# se7en.net
KiCad netlist of a schematic drawn in EAGLE
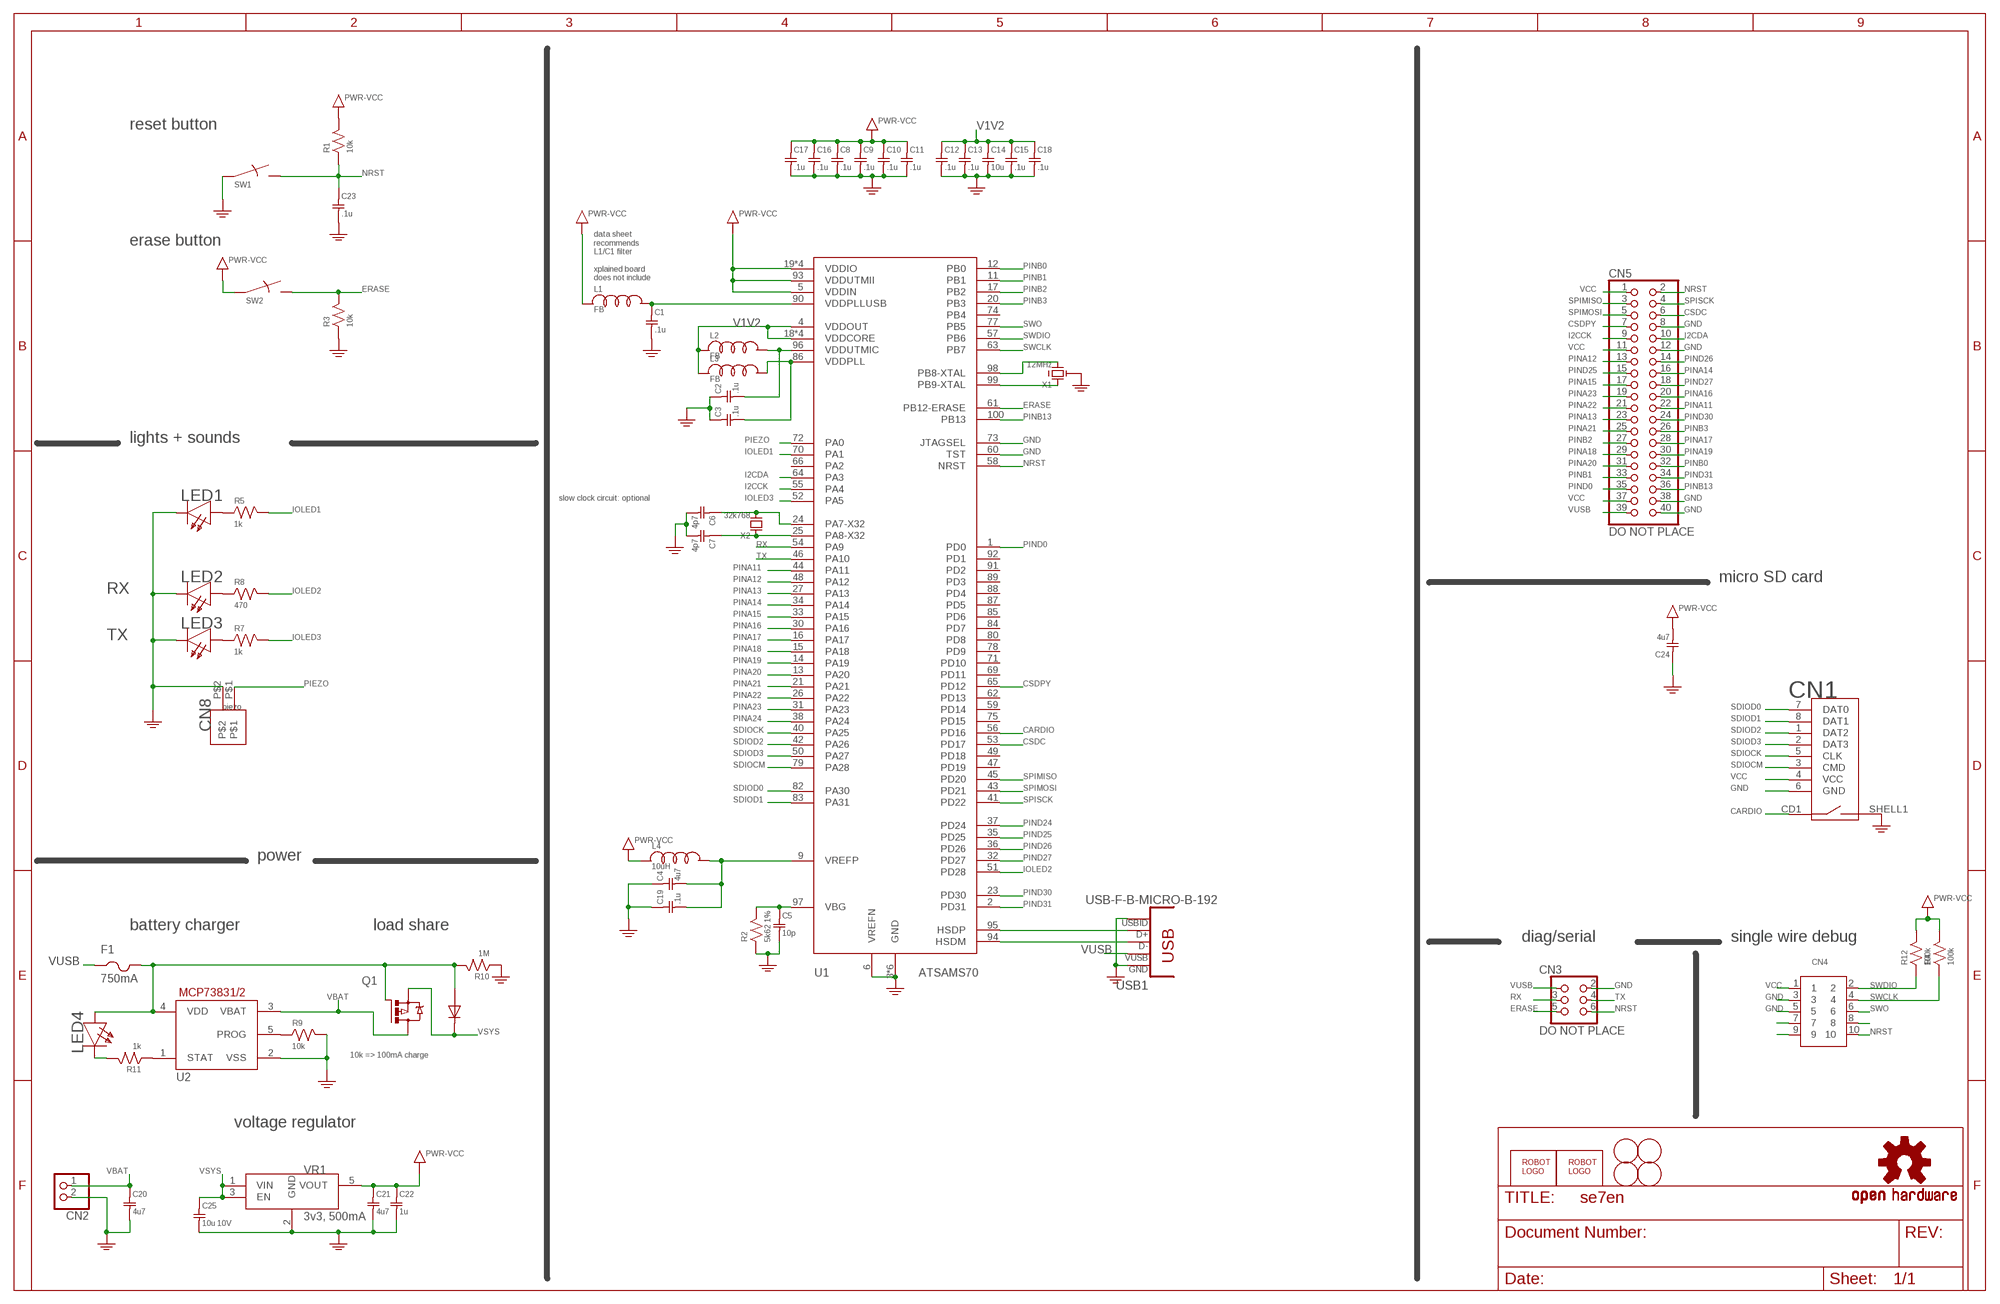
[diagram p0: schematic, sheet 1]

(export (version "E")
  (design (tool "Eeschema 10.0.6"))
  (components
    (comp (ref "C1")
      (value ".1u")
      (footprint "eagle-import:SMD0402")
      (libsource (lib "eagle-import") (part "C-0402"))
    )
    (comp (ref "C2")
      (value ".1u")
      (footprint "eagle-import:SMD0402")
      (libsource (lib "eagle-import") (part "C-0402"))
    )
    (comp (ref "C3")
      (value ".1u")
      (footprint "eagle-import:SMD0402")
      (libsource (lib "eagle-import") (part "C-0402"))
    )
    (comp (ref "C4")
      (value "4u7")
      (footprint "eagle-import:SMD0603")
      (libsource (lib "eagle-import") (part "C0603"))
    )
    (comp (ref "C5")
      (value "10p")
      (footprint "eagle-import:SMD0402")
      (libsource (lib "eagle-import") (part "C-0402"))
    )
    (comp (ref "C6")
      (value "4p7")
      (footprint "eagle-import:SMD0402")
      (libsource (lib "eagle-import") (part "C-0402"))
    )
    (comp (ref "C7")
      (value "4p7")
      (footprint "eagle-import:SMD0402")
      (libsource (lib "eagle-import") (part "C-0402"))
    )
    (comp (ref "C8")
      (value ".1u")
      (footprint "eagle-import:SMD0402")
      (libsource (lib "eagle-import") (part "C-0402"))
    )
    (comp (ref "C9")
      (value ".1u")
      (footprint "eagle-import:SMD0402")
      (libsource (lib "eagle-import") (part "C-0402"))
    )
    (comp (ref "C10")
      (value ".1u")
      (footprint "eagle-import:SMD0402")
      (libsource (lib "eagle-import") (part "C-0402"))
    )
    (comp (ref "C11")
      (value ".1u")
      (footprint "eagle-import:SMD0402")
      (libsource (lib "eagle-import") (part "C-0402"))
    )
    (comp (ref "C12")
      (value ".1u")
      (footprint "eagle-import:SMD0402")
      (libsource (lib "eagle-import") (part "C-0402"))
    )
    (comp (ref "C13")
      (value ".1u")
      (footprint "eagle-import:SMD0402")
      (libsource (lib "eagle-import") (part "C-0402"))
    )
    (comp (ref "C14")
      (value "10u")
      (footprint "eagle-import:SMD0603")
      (libsource (lib "eagle-import") (part "C0603"))
    )
    (comp (ref "C15")
      (value ".1u")
      (footprint "eagle-import:SMD0402")
      (libsource (lib "eagle-import") (part "C-0402"))
    )
    (comp (ref "C16")
      (value ".1u")
      (footprint "eagle-import:SMD0402")
      (libsource (lib "eagle-import") (part "C-0402"))
    )
    (comp (ref "C17")
      (value ".1u")
      (footprint "eagle-import:SMD0402")
      (libsource (lib "eagle-import") (part "C-0402"))
    )
    (comp (ref "C18")
      (value ".1u")
      (footprint "eagle-import:SMD0402")
      (libsource (lib "eagle-import") (part "C-0402"))
    )
    (comp (ref "C19")
      (value ".1u")
      (footprint "eagle-import:SMD0402")
      (libsource (lib "eagle-import") (part "C-0402"))
    )
    (comp (ref "C20")
      (value "4u7")
      (footprint "eagle-import:SMD0603")
      (libsource (lib "eagle-import") (part "C0603"))
    )
    (comp (ref "C21")
      (value "4u7")
      (footprint "eagle-import:SMD0603")
      (libsource (lib "eagle-import") (part "C0603"))
    )
    (comp (ref "C22")
      (value "1u")
      (footprint "eagle-import:SMD0603")
      (libsource (lib "eagle-import") (part "C0603"))
    )
    (comp (ref "C23")
      (value ".1u")
      (footprint "eagle-import:SMD0402")
      (libsource (lib "eagle-import") (part "C-0402"))
    )
    (comp (ref "C24")
      (value "4u7")
      (footprint "eagle-import:SMD0603")
      (libsource (lib "eagle-import") (part "C0603"))
    )
    (comp (ref "C25")
      (value "10u 10V")
      (footprint "eagle-import:SMD0603")
      (libsource (lib "eagle-import") (part "C0603"))
    )
    (comp (ref "CN1")
      (value "MICROSD-EJECT")
      (footprint "eagle-import:MICROSD_EJECTOR")
      (libsource (lib "eagle-import") (part "MICROSD-EJECT"))
    )
    (comp (ref "CN2")
      (value "JST_2PIN-SMT-RA")
      (footprint "eagle-import:JST-PH-2-SMT-RA")
      (libsource (lib "eagle-import") (part "JST_2PIN-SMT-RA"))
    )
    (comp (ref "CN3")
      (value "DO NOT PLACE")
      (footprint "eagle-import:HEADER-3X2-POGO")
      (libsource (lib "eagle-import") (part "HEADER-3X2-POGO"))
    )
    (comp (ref "CN4")
      (value "DO NOT PLACE")
      (footprint "eagle-import:M127-5X2-F")
      (libsource (lib "eagle-import") (part "HEADER-5X2-SMD-F"))
    )
    (comp (ref "CN5")
      (value "DO NOT PLACE")
      (footprint "eagle-import:2X20")
      (libsource (lib "eagle-import") (part "PINHD-2X20"))
    )
    (comp (ref "CN8")
      (value "DO NOT PLACE")
      (footprint "eagle-import:HEADER-1X2-THM-TIGHT")
      (libsource (lib "eagle-import") (part "HEADER-1X2M254"))
    )
    (comp (ref "F1")
      (value "750mA")
      (footprint "eagle-import:SMD1206")
      (libsource (lib "eagle-import") (part "FUSE"))
    )
    (comp (ref "L1")
      (value "FB")
      (footprint "eagle-import:SMD0402")
      (libsource (lib "eagle-import") (part "L-0402"))
    )
    (comp (ref "L2")
      (value "FB")
      (footprint "eagle-import:SMD0402")
      (libsource (lib "eagle-import") (part "L-0402"))
    )
    (comp (ref "L3")
      (value "FB")
      (footprint "eagle-import:SMD0402")
      (libsource (lib "eagle-import") (part "L-0402"))
    )
    (comp (ref "L4")
      (value "10uH")
      (footprint "eagle-import:SMD0603")
      (libsource (lib "eagle-import") (part "LSMD0603"))
    )
    (comp (ref "LED1")
      (value "white")
      (footprint "eagle-import:SMD0603D")
      (libsource (lib "eagle-import") (part "LED"))
    )
    (comp (ref "LED2")
      (value "green")
      (footprint "eagle-import:SMD0603D")
      (libsource (lib "eagle-import") (part "LED"))
    )
    (comp (ref "LED3")
      (value "orange")
      (footprint "eagle-import:SMD0603D")
      (libsource (lib "eagle-import") (part "LED"))
    )
    (comp (ref "LED4")
      (value "RED")
      (footprint "eagle-import:SMD0603D")
      (libsource (lib "eagle-import") (part "LED"))
    )
    (comp (ref "LOGO$1")
      (value "OSHW-LOGOM")
      (footprint "eagle-import:OSHW-LOGO-M")
      (libsource (lib "eagle-import") (part "OSHW-LOGOM"))
    )
    (comp (ref "Q1")
      (value "FDC6392S")
      (footprint "eagle-import:SOT-23-6")
      (libsource (lib "eagle-import") (part "FDC6392S"))
    )
    (comp (ref "R1")
      (value "10k")
      (footprint "eagle-import:SMD0402")
      (libsource (lib "eagle-import") (part "R-0402"))
    )
    (comp (ref "R2")
      (value "5k62 1%")
      (footprint "eagle-import:SMD0402")
      (libsource (lib "eagle-import") (part "R-0402"))
    )
    (comp (ref "R3")
      (value "10k")
      (footprint "eagle-import:SMD0402")
      (libsource (lib "eagle-import") (part "R-0402"))
    )
    (comp (ref "R4")
      (value "100k")
      (footprint "eagle-import:SMD0402")
      (libsource (lib "eagle-import") (part "R-0402"))
    )
    (comp (ref "R5")
      (value "1k")
      (footprint "eagle-import:SMD0402")
      (libsource (lib "eagle-import") (part "R-0402"))
    )
    (comp (ref "R7")
      (value "1k")
      (footprint "eagle-import:SMD0402")
      (libsource (lib "eagle-import") (part "R-0402"))
    )
    (comp (ref "R8")
      (value "470")
      (footprint "eagle-import:SMD0402")
      (libsource (lib "eagle-import") (part "R-0402"))
    )
    (comp (ref "R9")
      (value "10k")
      (footprint "eagle-import:SMD0402")
      (libsource (lib "eagle-import") (part "R-0402"))
    )
    (comp (ref "R10")
      (value "1M")
      (footprint "eagle-import:SMD0402")
      (libsource (lib "eagle-import") (part "R-0402"))
    )
    (comp (ref "R11")
      (value "1k")
      (footprint "eagle-import:SMD0402")
      (libsource (lib "eagle-import") (part "R-0402"))
    )
    (comp (ref "R12")
      (value "100k")
      (footprint "eagle-import:SMD0402")
      (libsource (lib "eagle-import") (part "R-0402"))
    )
    (comp (ref "SW1")
      (value "SWITCHKMR211")
      (footprint "eagle-import:KMR211")
      (libsource (lib "eagle-import") (part "SWITCHKMR211"))
    )
    (comp (ref "SW2")
      (value "SWITCHKMR211")
      (footprint "eagle-import:KMR211")
      (libsource (lib "eagle-import") (part "SWITCHKMR211"))
    )
    (comp (ref "U$1")
      (value "ROBOTMAN-LOGO2")
      (footprint "eagle-import:ROBOTMAN-LOGO2")
      (libsource (lib "eagle-import") (part "ROBOTMAN-LOGO2"))
    )
    (comp (ref "U$2")
      (value "FIDUCIAL")
      (footprint "eagle-import:FIDUCIAL_1MM")
      (libsource (lib "eagle-import") (part "FIDUCIAL"))
    )
    (comp (ref "U$3")
      (value "ROBOTMAN-LOGO2")
      (footprint "eagle-import:ROBOTMAN-LOGO2")
      (libsource (lib "eagle-import") (part "ROBOTMAN-LOGO2"))
    )
    (comp (ref "U$4")
      (value "FIDUCIAL")
      (footprint "eagle-import:FIDUCIAL_1MM")
      (libsource (lib "eagle-import") (part "FIDUCIAL"))
    )
    (comp (ref "U$5")
      (value "FIDUCIAL")
      (footprint "eagle-import:FIDUCIAL_1MM")
      (libsource (lib "eagle-import") (part "FIDUCIAL"))
    )
    (comp (ref "U$6")
      (value "FIDUCIAL")
      (footprint "eagle-import:FIDUCIAL_1MM")
      (libsource (lib "eagle-import") (part "FIDUCIAL"))
    )
    (comp (ref "U1")
      (value "ATSAMS70")
      (footprint "eagle-import:TQFP-100-14X14MM")
      (libsource (lib "eagle-import") (part "ATSAME70"))
    )
    (comp (ref "U2")
      (value "MCP73831")
      (footprint "eagle-import:SOT-23-5")
      (libsource (lib "eagle-import") (part "MCP73831"))
    )
    (comp (ref "USB1")
      (value "USB-F-B-MICRO-B-192")
      (footprint "eagle-import:USB-MICRO-B-192")
      (libsource (lib "eagle-import") (part "USB-F-B-MICRO-B-192"))
    )
    (comp (ref "VR1")
      (value "3v3, 500mA")
      (footprint "eagle-import:SOT-23-5")
      (libsource (lib "eagle-import") (part "REGULATOR4-SOT23"))
    )
    (comp (ref "X1")
      (value "12MHz")
      (footprint "eagle-import:RESONATOR-CSTCE")
      (libsource (lib "eagle-import") (part "RESONATORCTCE"))
    )
    (comp (ref "X2")
      (value "32k768")
      (footprint "eagle-import:XTAL-32X15")
      (libsource (lib "eagle-import") (part "XTAL32X15"))
    )
  )
  (nets
    (net (code "1") (name "/CARDIO") (class "Default")
      (node (ref "CN1") (pin "CD1") (pinfunction "SW1_CD1") (pintype "bidirectional"))
      (node (ref "U1") (pin "56") (pinfunction "PD16_56") (pintype "bidirectional"))
    )
    (net (code "2") (name "/CSDC") (class "Default")
      (node (ref "CN5") (pin "6") (pinfunction "6_6") (pintype "passive"))
      (node (ref "U1") (pin "53") (pinfunction "PD17_53") (pintype "bidirectional"))
    )
    (net (code "3") (name "/CSDPY") (class "Default")
      (node (ref "CN5") (pin "7") (pinfunction "7_7") (pintype "passive"))
      (node (ref "U1") (pin "65") (pinfunction "PD12_65") (pintype "bidirectional"))
    )
    (net (code "4") (name "/ERASE") (class "Default")
      (node (ref "CN3") (pin "5") (pinfunction "P$5_5") (pintype "passive"))
      (node (ref "R3") (pin "2") (pinfunction "P$2_2") (pintype "passive"))
      (node (ref "SW2") (pin "2") (pinfunction "P$2_2") (pintype "passive"))
      (node (ref "SW2") (pin "4") (pinfunction "P$2_4") (pintype "passive"))
      (node (ref "U1") (pin "61") (pinfunction "PB12-ERASE_61") (pintype "bidirectional"))
    )
    (net (code "5") (name "/I2CCK") (class "Default")
      (node (ref "CN5") (pin "9") (pinfunction "9_9") (pintype "passive"))
      (node (ref "U1") (pin "55") (pinfunction "PA4_55") (pintype "bidirectional"))
    )
    (net (code "6") (name "/I2CDA") (class "Default")
      (node (ref "CN5") (pin "10") (pinfunction "10_10") (pintype "passive"))
      (node (ref "U1") (pin "64") (pinfunction "PA3_64") (pintype "bidirectional"))
    )
    (net (code "7") (name "/IOLED1") (class "Default")
      (node (ref "R5") (pin "2") (pinfunction "P$2_2") (pintype "passive"))
      (node (ref "U1") (pin "70") (pinfunction "PA1_70") (pintype "bidirectional"))
    )
    (net (code "8") (name "/IOLED2") (class "Default")
      (node (ref "R8") (pin "2") (pinfunction "P$2_2") (pintype "passive"))
      (node (ref "U1") (pin "51") (pinfunction "PD28_51") (pintype "bidirectional"))
    )
    (net (code "9") (name "/IOLED3") (class "Default")
      (node (ref "R7") (pin "2") (pinfunction "P$2_2") (pintype "passive"))
      (node (ref "U1") (pin "52") (pinfunction "PA5_52") (pintype "bidirectional"))
    )
    (net (code "10") (name "/NRST") (class "Default")
      (node (ref "C23") (pin "1") (pinfunction "P$1_1") (pintype "passive"))
      (node (ref "CN3") (pin "6") (pinfunction "P$6_6") (pintype "passive"))
      (node (ref "CN4") (pin "10") (pinfunction "10_10") (pintype "passive"))
      (node (ref "CN5") (pin "2") (pinfunction "2_2") (pintype "passive"))
      (node (ref "R1") (pin "1") (pinfunction "P$1_1") (pintype "passive"))
      (node (ref "SW1") (pin "2") (pinfunction "P$2_2") (pintype "passive"))
      (node (ref "SW1") (pin "4") (pinfunction "P$2_4") (pintype "passive"))
      (node (ref "U1") (pin "58") (pinfunction "NRST_58") (pintype "bidirectional"))
    )
    (net (code "11") (name "/PIEZO") (class "Default")
      (node (ref "CN8") (pin "P$1") (pinfunction "P$1_P$1") (pintype "bidirectional"))
      (node (ref "U1") (pin "72") (pinfunction "PA0_72") (pintype "bidirectional"))
    )
    (net (code "12") (name "/PINA11") (class "Default")
      (node (ref "CN5") (pin "22") (pinfunction "22_22") (pintype "passive"))
      (node (ref "U1") (pin "44") (pinfunction "PA11_44") (pintype "bidirectional"))
    )
    (net (code "13") (name "/PINA12") (class "Default")
      (node (ref "CN5") (pin "13") (pinfunction "13_13") (pintype "passive"))
      (node (ref "U1") (pin "48") (pinfunction "PA12_48") (pintype "bidirectional"))
    )
    (net (code "14") (name "/PINA13") (class "Default")
      (node (ref "CN5") (pin "23") (pinfunction "23_23") (pintype "passive"))
      (node (ref "U1") (pin "27") (pinfunction "PA13_27") (pintype "bidirectional"))
    )
    (net (code "15") (name "/PINA14") (class "Default")
      (node (ref "CN5") (pin "16") (pinfunction "16_16") (pintype "passive"))
      (node (ref "U1") (pin "34") (pinfunction "PA14_34") (pintype "bidirectional"))
    )
    (net (code "16") (name "/PINA15") (class "Default")
      (node (ref "CN5") (pin "17") (pinfunction "17_17") (pintype "passive"))
      (node (ref "U1") (pin "33") (pinfunction "PA15_33") (pintype "bidirectional"))
    )
    (net (code "17") (name "/PINA16") (class "Default")
      (node (ref "CN5") (pin "20") (pinfunction "20_20") (pintype "passive"))
      (node (ref "U1") (pin "30") (pinfunction "PA16_30") (pintype "bidirectional"))
    )
    (net (code "18") (name "/PINA17") (class "Default")
      (node (ref "CN5") (pin "28") (pinfunction "28_28") (pintype "passive"))
      (node (ref "U1") (pin "16") (pinfunction "PA17_16") (pintype "bidirectional"))
    )
    (net (code "19") (name "/PINA18") (class "Default")
      (node (ref "CN5") (pin "29") (pinfunction "29_29") (pintype "passive"))
      (node (ref "U1") (pin "15") (pinfunction "PA18_15") (pintype "bidirectional"))
    )
    (net (code "20") (name "/PINA19") (class "Default")
      (node (ref "CN5") (pin "30") (pinfunction "30_30") (pintype "passive"))
      (node (ref "U1") (pin "14") (pinfunction "PA19_14") (pintype "bidirectional"))
    )
    (net (code "21") (name "/PINA20") (class "Default")
      (node (ref "CN5") (pin "31") (pinfunction "31_31") (pintype "passive"))
      (node (ref "U1") (pin "13") (pinfunction "PA20_13") (pintype "bidirectional"))
    )
    (net (code "22") (name "/PINA21") (class "Default")
      (node (ref "CN5") (pin "25") (pinfunction "25_25") (pintype "passive"))
      (node (ref "U1") (pin "21") (pinfunction "PA21_21") (pintype "bidirectional"))
    )
    (net (code "23") (name "/PINA22") (class "Default")
      (node (ref "CN5") (pin "21") (pinfunction "21_21") (pintype "passive"))
      (node (ref "U1") (pin "26") (pinfunction "PA22_26") (pintype "bidirectional"))
    )
    (net (code "24") (name "/PINA23") (class "Default")
      (node (ref "CN5") (pin "19") (pinfunction "19_19") (pintype "passive"))
      (node (ref "U1") (pin "31") (pinfunction "PA23_31") (pintype "bidirectional"))
    )
    (net (code "25") (name "/PINA24") (class "Default")
      (node (ref "U1") (pin "38") (pinfunction "PA24_38") (pintype "bidirectional"))
    )
    (net (code "26") (name "/PINB0") (class "Default")
      (node (ref "CN5") (pin "32") (pinfunction "32_32") (pintype "passive"))
      (node (ref "U1") (pin "12") (pinfunction "PB0_12") (pintype "bidirectional"))
    )
    (net (code "27") (name "/PINB1") (class "Default")
      (node (ref "CN5") (pin "33") (pinfunction "33_33") (pintype "passive"))
      (node (ref "U1") (pin "11") (pinfunction "PB1_11") (pintype "bidirectional"))
    )
    (net (code "28") (name "/PINB2") (class "Default")
      (node (ref "CN5") (pin "27") (pinfunction "27_27") (pintype "passive"))
      (node (ref "U1") (pin "17") (pinfunction "PB2_17") (pintype "bidirectional"))
    )
    (net (code "29") (name "/PINB3") (class "Default")
      (node (ref "CN5") (pin "26") (pinfunction "26_26") (pintype "passive"))
      (node (ref "U1") (pin "20") (pinfunction "PB3_20") (pintype "bidirectional"))
    )
    (net (code "30") (name "/PINB13") (class "Default")
      (node (ref "CN5") (pin "36") (pinfunction "36_36") (pintype "passive"))
      (node (ref "U1") (pin "100") (pinfunction "PB13_100") (pintype "bidirectional"))
    )
    (net (code "31") (name "/PIND0") (class "Default")
      (node (ref "CN5") (pin "35") (pinfunction "35_35") (pintype "passive"))
      (node (ref "U1") (pin "1") (pinfunction "PD0_1") (pintype "bidirectional"))
    )
    (net (code "32") (name "/PIND24") (class "Default")
      (node (ref "U1") (pin "37") (pinfunction "PD24_37") (pintype "bidirectional"))
    )
    (net (code "33") (name "/PIND25") (class "Default")
      (node (ref "CN5") (pin "15") (pinfunction "15_15") (pintype "passive"))
      (node (ref "U1") (pin "35") (pinfunction "PD25_35") (pintype "bidirectional"))
    )
    (net (code "34") (name "/PIND26") (class "Default")
      (node (ref "CN5") (pin "14") (pinfunction "14_14") (pintype "passive"))
      (node (ref "U1") (pin "36") (pinfunction "PD26_36") (pintype "bidirectional"))
    )
    (net (code "35") (name "/PIND27") (class "Default")
      (node (ref "CN5") (pin "18") (pinfunction "18_18") (pintype "passive"))
      (node (ref "U1") (pin "32") (pinfunction "PD27_32") (pintype "bidirectional"))
    )
    (net (code "36") (name "/PIND30") (class "Default")
      (node (ref "CN5") (pin "24") (pinfunction "24_24") (pintype "passive"))
      (node (ref "U1") (pin "23") (pinfunction "PD30_23") (pintype "bidirectional"))
    )
    (net (code "37") (name "/PIND31") (class "Default")
      (node (ref "CN5") (pin "34") (pinfunction "34_34") (pintype "passive"))
      (node (ref "U1") (pin "2") (pinfunction "PD31_2") (pintype "bidirectional"))
    )
    (net (code "38") (name "/RX") (class "Default")
      (node (ref "CN3") (pin "3") (pinfunction "P$3_3") (pintype "passive"))
      (node (ref "U1") (pin "54") (pinfunction "PA9_54") (pintype "bidirectional"))
    )
    (net (code "39") (name "/SDIOCK") (class "Default")
      (node (ref "CN1") (pin "5") (pinfunction "CLK_5") (pintype "bidirectional"))
      (node (ref "U1") (pin "40") (pinfunction "PA25_40") (pintype "bidirectional"))
    )
    (net (code "40") (name "/SDIOCM") (class "Default")
      (node (ref "CN1") (pin "3") (pinfunction "CMD_3") (pintype "bidirectional"))
      (node (ref "U1") (pin "79") (pinfunction "PA28_79") (pintype "bidirectional"))
    )
    (net (code "41") (name "/SDIOD0") (class "Default")
      (node (ref "CN1") (pin "7") (pinfunction "DAT0_7") (pintype "bidirectional"))
      (node (ref "U1") (pin "82") (pinfunction "PA30_82") (pintype "bidirectional"))
    )
    (net (code "42") (name "/SDIOD1") (class "Default")
      (node (ref "CN1") (pin "8") (pinfunction "DAT1_8") (pintype "bidirectional"))
      (node (ref "U1") (pin "83") (pinfunction "PA31_83") (pintype "bidirectional"))
    )
    (net (code "43") (name "/SDIOD2") (class "Default")
      (node (ref "CN1") (pin "1") (pinfunction "DAT2_1") (pintype "bidirectional"))
      (node (ref "U1") (pin "42") (pinfunction "PA26_42") (pintype "bidirectional"))
    )
    (net (code "44") (name "/SDIOD3") (class "Default")
      (node (ref "CN1") (pin "2") (pinfunction "DAT3_2") (pintype "bidirectional"))
      (node (ref "U1") (pin "50") (pinfunction "PA27_50") (pintype "bidirectional"))
    )
    (net (code "45") (name "/SPIMISO") (class "Default")
      (node (ref "CN5") (pin "3") (pinfunction "3_3") (pintype "passive"))
      (node (ref "U1") (pin "45") (pinfunction "PD20_45") (pintype "bidirectional"))
    )
    (net (code "46") (name "/SPIMOSI") (class "Default")
      (node (ref "CN5") (pin "5") (pinfunction "5_5") (pintype "passive"))
      (node (ref "U1") (pin "43") (pinfunction "PD21_43") (pintype "bidirectional"))
    )
    (net (code "47") (name "/SPISCK") (class "Default")
      (node (ref "CN5") (pin "4") (pinfunction "4_4") (pintype "passive"))
      (node (ref "U1") (pin "41") (pinfunction "PD22_41") (pintype "bidirectional"))
    )
    (net (code "48") (name "/SWCLK") (class "Default")
      (node (ref "CN4") (pin "4") (pinfunction "4_4") (pintype "passive"))
      (node (ref "R4") (pin "1") (pinfunction "P$1_1") (pintype "passive"))
      (node (ref "U1") (pin "63") (pinfunction "PB7_63") (pintype "bidirectional"))
    )
    (net (code "49") (name "/SWDIO") (class "Default")
      (node (ref "CN4") (pin "2") (pinfunction "2_2") (pintype "passive"))
      (node (ref "R12") (pin "1") (pinfunction "P$1_1") (pintype "passive"))
      (node (ref "U1") (pin "57") (pinfunction "PB6_57") (pintype "bidirectional"))
    )
    (net (code "50") (name "/SWO") (class "Default")
      (node (ref "CN4") (pin "6") (pinfunction "6_6") (pintype "passive"))
      (node (ref "U1") (pin "77") (pinfunction "PB5_77") (pintype "bidirectional"))
    )
    (net (code "51") (name "/TX") (class "Default")
      (node (ref "CN3") (pin "4") (pinfunction "P$4_4") (pintype "passive"))
      (node (ref "U1") (pin "46") (pinfunction "PA10_46") (pintype "bidirectional"))
    )
    (net (code "52") (name "/V1V2") (class "Default")
      (node (ref "C12") (pin "1") (pinfunction "P$1_1") (pintype "passive"))
      (node (ref "C13") (pin "1") (pinfunction "P$1_1") (pintype "passive"))
      (node (ref "C14") (pin "1") (pinfunction "P$1_1") (pintype "passive"))
      (node (ref "C15") (pin "1") (pinfunction "P$1_1") (pintype "passive"))
      (node (ref "C18") (pin "1") (pinfunction "P$1_1") (pintype "passive"))
      (node (ref "L2") (pin "1") (pinfunction "P$1_1") (pintype "passive"))
      (node (ref "L3") (pin "1") (pinfunction "P$1_1") (pintype "passive"))
      (node (ref "U1") (pin "18") (pinfunction "VDDCORE_18") (pintype "bidirectional"))
      (node (ref "U1") (pin "22") (pinfunction "VDDCORE_22") (pintype "bidirectional"))
      (node (ref "U1") (pin "39") (pinfunction "VDDCORE_39") (pintype "bidirectional"))
      (node (ref "U1") (pin "4") (pinfunction "VDDOUT_4") (pintype "bidirectional"))
      (node (ref "U1") (pin "76") (pinfunction "VDDCORE_76") (pintype "bidirectional"))
    )
    (net (code "53") (name "/VBAT") (class "Default")
      (node (ref "C20") (pin "1") (pinfunction "P$1_1") (pintype "passive"))
      (node (ref "CN2") (pin "1") (pinfunction "2_1") (pintype "passive"))
      (node (ref "Q1") (pin "4") (pinfunction "D_4") (pintype "passive"))
      (node (ref "U2") (pin "3") (pinfunction "VBAT_3") (pintype "bidirectional"))
    )
    (net (code "54") (name "/VSYS") (class "Default")
      (node (ref "C25") (pin "1") (pinfunction "P$1_1") (pintype "passive"))
      (node (ref "Q1") (pin "2") (pinfunction "S_2") (pintype "passive"))
      (node (ref "Q1") (pin "6") (pinfunction "C_6") (pintype "passive"))
      (node (ref "VR1") (pin "1") (pinfunction "VIN_1") (pintype "bidirectional"))
      (node (ref "VR1") (pin "3") (pinfunction "EN_3") (pintype "bidirectional"))
    )
    (net (code "55") (name "/VUSB") (class "Default")
      (node (ref "CN3") (pin "1") (pinfunction "P$1_1") (pintype "passive"))
      (node (ref "CN5") (pin "39") (pinfunction "39_39") (pintype "passive"))
      (node (ref "F1") (pin "1") (pinfunction "1_1") (pintype "passive"))
      (node (ref "USB1") (pin "P1") (pinfunction "VUSB_P1") (pintype "bidirectional"))
    )
    (net (code "56") (name "Net-(C1-P$1)") (class "Default")
      (node (ref "C1") (pin "1") (pinfunction "P$1_1") (pintype "passive"))
      (node (ref "L1") (pin "2") (pinfunction "P$2_2") (pintype "passive"))
      (node (ref "U1") (pin "90") (pinfunction "VDDPLLUSB_90") (pintype "bidirectional"))
    )
    (net (code "57") (name "Net-(C2-P$2)") (class "Default")
      (node (ref "C2") (pin "2") (pinfunction "P$2_2") (pintype "passive"))
      (node (ref "L2") (pin "2") (pinfunction "P$2_2") (pintype "passive"))
      (node (ref "U1") (pin "96") (pinfunction "VDDUTMIC_96") (pintype "bidirectional"))
    )
    (net (code "58") (name "Net-(C3-P$2)") (class "Default")
      (node (ref "C3") (pin "2") (pinfunction "P$2_2") (pintype "passive"))
      (node (ref "L3") (pin "2") (pinfunction "P$2_2") (pintype "passive"))
      (node (ref "U1") (pin "86") (pinfunction "VDDPLL_86") (pintype "bidirectional"))
    )
    (net (code "59") (name "Net-(C5-P$1)") (class "Default")
      (node (ref "C5") (pin "1") (pinfunction "P$1_1") (pintype "passive"))
      (node (ref "R2") (pin "2") (pinfunction "P$2_2") (pintype "passive"))
      (node (ref "U1") (pin "97") (pinfunction "VBG_97") (pintype "bidirectional"))
    )
    (net (code "60") (name "Net-(C6-P$1)") (class "Default")
      (node (ref "C6") (pin "1") (pinfunction "P$1_1") (pintype "passive"))
      (node (ref "U1") (pin "24") (pinfunction "PA7-X32_24") (pintype "bidirectional"))
      (node (ref "X2") (pin "P$2") (pinfunction "P$2_P$2") (pintype "passive"))
    )
    (net (code "61") (name "Net-(C7-P$1)") (class "Default")
      (node (ref "C7") (pin "1") (pinfunction "P$1_1") (pintype "passive"))
      (node (ref "U1") (pin "25") (pinfunction "PA8-X32_25") (pintype "bidirectional"))
      (node (ref "X2") (pin "P$1") (pinfunction "P$1_P$1") (pintype "passive"))
    )
    (net (code "62") (name "Net-(C19-P$2)") (class "Default")
      (node (ref "C19") (pin "2") (pinfunction "P$2_2") (pintype "passive"))
      (node (ref "C4") (pin "2") (pinfunction "P$2_2") (pintype "passive"))
      (node (ref "L4") (pin "2") (pinfunction "P$2_2") (pintype "passive"))
      (node (ref "U1") (pin "9") (pinfunction "VREFP_9") (pintype "bidirectional"))
    )
    (net (code "63") (name "Net-(Q1-A)") (class "Default")
      (node (ref "F1") (pin "2") (pinfunction "2_2") (pintype "passive"))
      (node (ref "LED4") (pin "A") (pinfunction "A_A") (pintype "passive"))
      (node (ref "Q1") (pin "1") (pinfunction "A_1") (pintype "passive"))
      (node (ref "Q1") (pin "3") (pinfunction "G_3") (pintype "passive"))
      (node (ref "R10") (pin "2") (pinfunction "P$2_2") (pintype "passive"))
      (node (ref "U2") (pin "4") (pinfunction "VDD_4") (pintype "power_in"))
    )
    (net (code "64") (name "Net-(R5-P$1)") (class "Default")
      (node (ref "LED1") (pin "A") (pinfunction "A_A") (pintype "passive"))
      (node (ref "R5") (pin "1") (pinfunction "P$1_1") (pintype "passive"))
    )
    (net (code "65") (name "Net-(R7-P$1)") (class "Default")
      (node (ref "LED3") (pin "A") (pinfunction "A_A") (pintype "passive"))
      (node (ref "R7") (pin "1") (pinfunction "P$1_1") (pintype "passive"))
    )
    (net (code "66") (name "Net-(R8-P$1)") (class "Default")
      (node (ref "LED2") (pin "A") (pinfunction "A_A") (pintype "passive"))
      (node (ref "R8") (pin "1") (pinfunction "P$1_1") (pintype "passive"))
    )
    (net (code "67") (name "Net-(R9-P$1)") (class "Default")
      (node (ref "R9") (pin "1") (pinfunction "P$1_1") (pintype "passive"))
      (node (ref "U2") (pin "5") (pinfunction "PROG_5") (pintype "input"))
    )
    (net (code "68") (name "Net-(R11-P$1)") (class "Default")
      (node (ref "R11") (pin "1") (pinfunction "P$1_1") (pintype "passive"))
      (node (ref "U2") (pin "1") (pinfunction "STAT_1") (pintype "output"))
    )
    (net (code "69") (name "Net-(R11-P$2)") (class "Default")
      (node (ref "LED4") (pin "C") (pinfunction "C_C") (pintype "passive"))
      (node (ref "R11") (pin "2") (pinfunction "P$2_2") (pintype "passive"))
    )
    (net (code "70") (name "Net-(U1-HSDM)") (class "Default")
      (node (ref "U1") (pin "94") (pinfunction "HSDM_94") (pintype "bidirectional"))
      (node (ref "USB1") (pin "P2") (pinfunction "D-_P2") (pintype "bidirectional"))
    )
    (net (code "71") (name "Net-(U1-HSDP)") (class "Default")
      (node (ref "U1") (pin "95") (pinfunction "HSDP_95") (pintype "bidirectional"))
      (node (ref "USB1") (pin "P3") (pinfunction "D+_P3") (pintype "bidirectional"))
    )
    (net (code "72") (name "Net-(U1-PB8-XTAL)") (class "Default")
      (node (ref "U1") (pin "98") (pinfunction "PB8-XTAL_98") (pintype "bidirectional"))
      (node (ref "X1") (pin "3") (pinfunction "X2_3") (pintype "passive"))
    )
    (net (code "73") (name "Net-(U1-PB9-XTAL)") (class "Default")
      (node (ref "U1") (pin "99") (pinfunction "PB9-XTAL_99") (pintype "bidirectional"))
      (node (ref "X1") (pin "1") (pinfunction "X1_1") (pintype "passive"))
    )
    (net (code "74") (name "PWR-GND") (class "Default")
      (node (ref "C1") (pin "2") (pinfunction "P$2_2") (pintype "passive"))
      (node (ref "C10") (pin "2") (pinfunction "P$2_2") (pintype "passive"))
      (node (ref "C11") (pin "2") (pinfunction "P$2_2") (pintype "passive"))
      (node (ref "C12") (pin "2") (pinfunction "P$2_2") (pintype "passive"))
      (node (ref "C13") (pin "2") (pinfunction "P$2_2") (pintype "passive"))
      (node (ref "C14") (pin "2") (pinfunction "P$2_2") (pintype "passive"))
      (node (ref "C15") (pin "2") (pinfunction "P$2_2") (pintype "passive"))
      (node (ref "C16") (pin "2") (pinfunction "P$2_2") (pintype "passive"))
      (node (ref "C17") (pin "2") (pinfunction "P$2_2") (pintype "passive"))
      (node (ref "C18") (pin "2") (pinfunction "P$2_2") (pintype "passive"))
      (node (ref "C19") (pin "1") (pinfunction "P$1_1") (pintype "passive"))
      (node (ref "C2") (pin "1") (pinfunction "P$1_1") (pintype "passive"))
      (node (ref "C20") (pin "2") (pinfunction "P$2_2") (pintype "passive"))
      (node (ref "C21") (pin "2") (pinfunction "P$2_2") (pintype "passive"))
      (node (ref "C22") (pin "2") (pinfunction "P$2_2") (pintype "passive"))
      (node (ref "C23") (pin "2") (pinfunction "P$2_2") (pintype "passive"))
      (node (ref "C24") (pin "1") (pinfunction "P$1_1") (pintype "passive"))
      (node (ref "C25") (pin "2") (pinfunction "P$2_2") (pintype "passive"))
      (node (ref "C3") (pin "1") (pinfunction "P$1_1") (pintype "passive"))
      (node (ref "C4") (pin "1") (pinfunction "P$1_1") (pintype "passive"))
      (node (ref "C5") (pin "2") (pinfunction "P$2_2") (pintype "passive"))
      (node (ref "C6") (pin "2") (pinfunction "P$2_2") (pintype "passive"))
      (node (ref "C7") (pin "2") (pinfunction "P$2_2") (pintype "passive"))
      (node (ref "C8") (pin "2") (pinfunction "P$2_2") (pintype "passive"))
      (node (ref "C9") (pin "2") (pinfunction "P$2_2") (pintype "passive"))
      (node (ref "CN1") (pin "6") (pinfunction "GND_6") (pintype "bidirectional"))
      (node (ref "CN1") (pin "SHELL1") (pinfunction "SW2_SHELL1") (pintype "bidirectional"))
      (node (ref "CN2") (pin "2") (pinfunction "1_2") (pintype "passive"))
      (node (ref "CN3") (pin "2") (pinfunction "P$2_2") (pintype "passive"))
      (node (ref "CN4") (pin "3") (pinfunction "3_3") (pintype "passive"))
      (node (ref "CN4") (pin "5") (pinfunction "5_5") (pintype "passive"))
      (node (ref "CN5") (pin "12") (pinfunction "12_12") (pintype "passive"))
      (node (ref "CN5") (pin "38") (pinfunction "38_38") (pintype "passive"))
      (node (ref "CN5") (pin "40") (pinfunction "40_40") (pintype "passive"))
      (node (ref "CN5") (pin "8") (pinfunction "8_8") (pintype "passive"))
      (node (ref "CN8") (pin "P$2") (pinfunction "P$2_P$2") (pintype "bidirectional"))
      (node (ref "LED1") (pin "C") (pinfunction "C_C") (pintype "passive"))
      (node (ref "LED2") (pin "C") (pinfunction "C_C") (pintype "passive"))
      (node (ref "LED3") (pin "C") (pinfunction "C_C") (pintype "passive"))
      (node (ref "R10") (pin "1") (pinfunction "P$1_1") (pintype "passive"))
      (node (ref "R2") (pin "1") (pinfunction "P$1_1") (pintype "passive"))
      (node (ref "R3") (pin "1") (pinfunction "P$1_1") (pintype "passive"))
      (node (ref "R9") (pin "2") (pinfunction "P$2_2") (pintype "passive"))
      (node (ref "SW1") (pin "1") (pinfunction "P$1_1") (pintype "passive"))
      (node (ref "SW1") (pin "3") (pinfunction "P$1_3") (pintype "passive"))
      (node (ref "U1") (pin "10") (pinfunction "GND_10") (pintype "bidirectional"))
      (node (ref "U1") (pin "29") (pinfunction "GND_29") (pintype "bidirectional"))
      (node (ref "U1") (pin "3") (pinfunction "GND_3") (pintype "bidirectional"))
      (node (ref "U1") (pin "6") (pinfunction "VREFN_6") (pintype "bidirectional"))
      (node (ref "U1") (pin "60") (pinfunction "TST_60") (pintype "bidirectional"))
      (node (ref "U1") (pin "67") (pinfunction "GND_67") (pintype "bidirectional"))
      (node (ref "U1") (pin "7") (pinfunction "GND_7") (pintype "bidirectional"))
      (node (ref "U1") (pin "73") (pinfunction "JTAGSEL_73") (pintype "bidirectional"))
      (node (ref "U1") (pin "8") (pinfunction "GND_8") (pintype "bidirectional"))
      (node (ref "U2") (pin "2") (pinfunction "VSS_2") (pintype "power_in"))
      (node (ref "USB1") (pin "P4") (pinfunction "USBID_P4") (pintype "bidirectional"))
      (node (ref "USB1") (pin "P5") (pinfunction "GND_P5") (pintype "bidirectional"))
      (node (ref "VR1") (pin "2") (pinfunction "GND_2") (pintype "bidirectional"))
      (node (ref "X1") (pin "2") (pinfunction "G_2") (pintype "input"))
    )
    (net (code "75") (name "PWR-VCC") (class "Default")
      (node (ref "C10") (pin "1") (pinfunction "P$1_1") (pintype "passive"))
      (node (ref "C11") (pin "1") (pinfunction "P$1_1") (pintype "passive"))
      (node (ref "C16") (pin "1") (pinfunction "P$1_1") (pintype "passive"))
      (node (ref "C17") (pin "1") (pinfunction "P$1_1") (pintype "passive"))
      (node (ref "C21") (pin "1") (pinfunction "P$1_1") (pintype "passive"))
      (node (ref "C22") (pin "1") (pinfunction "P$1_1") (pintype "passive"))
      (node (ref "C24") (pin "2") (pinfunction "P$2_2") (pintype "passive"))
      (node (ref "C8") (pin "1") (pinfunction "P$1_1") (pintype "passive"))
      (node (ref "C9") (pin "1") (pinfunction "P$1_1") (pintype "passive"))
      (node (ref "CN1") (pin "4") (pinfunction "VCC_4") (pintype "bidirectional"))
      (node (ref "CN4") (pin "1") (pinfunction "1_1") (pintype "passive"))
      (node (ref "CN5") (pin "1") (pinfunction "1_1") (pintype "passive"))
      (node (ref "CN5") (pin "11") (pinfunction "11_11") (pintype "passive"))
      (node (ref "CN5") (pin "37") (pinfunction "37_37") (pintype "passive"))
      (node (ref "L1") (pin "1") (pinfunction "P$1_1") (pintype "passive"))
      (node (ref "L4") (pin "1") (pinfunction "P$1_1") (pintype "passive"))
      (node (ref "R1") (pin "2") (pinfunction "P$2_2") (pintype "passive"))
      (node (ref "R12") (pin "2") (pinfunction "P$2_2") (pintype "passive"))
      (node (ref "R4") (pin "2") (pinfunction "P$2_2") (pintype "passive"))
      (node (ref "SW2") (pin "1") (pinfunction "P$1_1") (pintype "passive"))
      (node (ref "SW2") (pin "3") (pinfunction "P$1_3") (pintype "passive"))
      (node (ref "U1") (pin "19") (pinfunction "VDDIO_19") (pintype "bidirectional"))
      (node (ref "U1") (pin "28") (pinfunction "VDDIO_28") (pintype "bidirectional"))
      (node (ref "U1") (pin "5") (pinfunction "VDDIN_5") (pintype "bidirectional"))
      (node (ref "U1") (pin "68") (pinfunction "VDDIO_68") (pintype "bidirectional"))
      (node (ref "U1") (pin "81") (pinfunction "VDDIO_81") (pintype "bidirectional"))
      (node (ref "U1") (pin "93") (pinfunction "VDDUTMII_93") (pintype "bidirectional"))
      (node (ref "VR1") (pin "5") (pinfunction "VOUT_5") (pintype "bidirectional"))
    )
    (net (code "76") (name "unconnected-(CN4-Pad7)") (class "Default")
      (node (ref "CN4") (pin "7") (pinfunction "7_7") (pintype "passive"))
    )
    (net (code "77") (name "unconnected-(CN4-Pad8)") (class "Default")
      (node (ref "CN4") (pin "8") (pinfunction "8_8") (pintype "passive"))
    )
    (net (code "78") (name "unconnected-(CN4-Pad9)") (class "Default")
      (node (ref "CN4") (pin "9") (pinfunction "9_9") (pintype "passive"))
    )
    (net (code "79") (name "unconnected-(U1-PA2-Pad66)") (class "Default")
      (node (ref "U1") (pin "66") (pinfunction "PA2_66") (pintype "bidirectional"))
    )
    (net (code "80") (name "unconnected-(U1-PB4-Pad74)") (class "Default")
      (node (ref "U1") (pin "74") (pinfunction "PB4_74") (pintype "bidirectional"))
    )
    (net (code "81") (name "unconnected-(U1-PD1-Pad92)") (class "Default")
      (node (ref "U1") (pin "92") (pinfunction "PD1_92") (pintype "bidirectional"))
    )
    (net (code "82") (name "unconnected-(U1-PD2-Pad91)") (class "Default")
      (node (ref "U1") (pin "91") (pinfunction "PD2_91") (pintype "bidirectional"))
    )
    (net (code "83") (name "unconnected-(U1-PD3-Pad89)") (class "Default")
      (node (ref "U1") (pin "89") (pinfunction "PD3_89") (pintype "bidirectional"))
    )
    (net (code "84") (name "unconnected-(U1-PD4-Pad88)") (class "Default")
      (node (ref "U1") (pin "88") (pinfunction "PD4_88") (pintype "bidirectional"))
    )
    (net (code "85") (name "unconnected-(U1-PD5-Pad87)") (class "Default")
      (node (ref "U1") (pin "87") (pinfunction "PD5_87") (pintype "bidirectional"))
    )
    (net (code "86") (name "unconnected-(U1-PD6-Pad85)") (class "Default")
      (node (ref "U1") (pin "85") (pinfunction "PD6_85") (pintype "bidirectional"))
    )
    (net (code "87") (name "unconnected-(U1-PD7-Pad84)") (class "Default")
      (node (ref "U1") (pin "84") (pinfunction "PD7_84") (pintype "bidirectional"))
    )
    (net (code "88") (name "unconnected-(U1-PD8-Pad80)") (class "Default")
      (node (ref "U1") (pin "80") (pinfunction "PD8_80") (pintype "bidirectional"))
    )
    (net (code "89") (name "unconnected-(U1-PD9-Pad78)") (class "Default")
      (node (ref "U1") (pin "78") (pinfunction "PD9_78") (pintype "bidirectional"))
    )
    (net (code "90") (name "unconnected-(U1-PD10-Pad71)") (class "Default")
      (node (ref "U1") (pin "71") (pinfunction "PD10_71") (pintype "bidirectional"))
    )
    (net (code "91") (name "unconnected-(U1-PD11-Pad69)") (class "Default")
      (node (ref "U1") (pin "69") (pinfunction "PD11_69") (pintype "bidirectional"))
    )
    (net (code "92") (name "unconnected-(U1-PD13-Pad62)") (class "Default")
      (node (ref "U1") (pin "62") (pinfunction "PD13_62") (pintype "bidirectional"))
    )
    (net (code "93") (name "unconnected-(U1-PD14-Pad59)") (class "Default")
      (node (ref "U1") (pin "59") (pinfunction "PD14_59") (pintype "bidirectional"))
    )
    (net (code "94") (name "unconnected-(U1-PD15-Pad75)") (class "Default")
      (node (ref "U1") (pin "75") (pinfunction "PD15_75") (pintype "bidirectional"))
    )
    (net (code "95") (name "unconnected-(U1-PD18-Pad49)") (class "Default")
      (node (ref "U1") (pin "49") (pinfunction "PD18_49") (pintype "bidirectional"))
    )
    (net (code "96") (name "unconnected-(U1-PD19-Pad47)") (class "Default")
      (node (ref "U1") (pin "47") (pinfunction "PD19_47") (pintype "bidirectional"))
    )
  )
)
